# Fan_Control.net
KiCad netlist of a schematic drawn in EAGLE
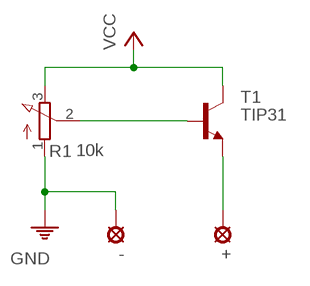
[diagram p0: schematic, sheet 1]

(export (version "E")
  (design (tool "Eeschema 10.0.6"))
  (components
    (comp (ref "+")
      (value "LSP10")
      (footprint "eagle-import:LSP10")
      (libsource (lib "eagle-import") (part "LSP10"))
    )
    (comp (ref "-")
      (value "LSP10")
      (footprint "eagle-import:LSP10")
      (libsource (lib "eagle-import") (part "LSP10"))
    )
    (comp (ref "R1")
      (value "10k")
      (footprint "eagle-import:3RP_1610N")
      (libsource (lib "eagle-import") (part "3RP/1610N"))
    )
    (comp (ref "T1")
      (value "TIP31")
      (footprint "eagle-import:TO220")
      (libsource (lib "eagle-import") (part "TIP31"))
    )
  )
  (nets
    (net (code "1") (name "GND") (class "Default")
      (node (ref "-") (pin "MP") (pinfunction "MP_MP") (pintype "passive"))
      (node (ref "R1") (pin "1") (pinfunction "A_1") (pintype "passive"))
    )
    (net (code "2") (name "Net-(R1-S)") (class "Default")
      (node (ref "R1") (pin "2") (pinfunction "S_2") (pintype "passive"))
      (node (ref "T1") (pin "1") (pinfunction "B_1") (pintype "passive"))
    )
    (net (code "3") (name "Net-(T1-E)") (class "Default")
      (node (ref "+") (pin "MP") (pinfunction "MP_MP") (pintype "passive"))
      (node (ref "T1") (pin "3") (pinfunction "E_3") (pintype "passive"))
    )
    (net (code "4") (name "VCC") (class "Default")
      (node (ref "R1") (pin "3") (pinfunction "E_3") (pintype "passive"))
      (node (ref "T1") (pin "2") (pinfunction "C_2") (pintype "passive"))
    )
  )
)
